# Sheet2.net
KiCad netlist of a schematic drawn in Altium Designer
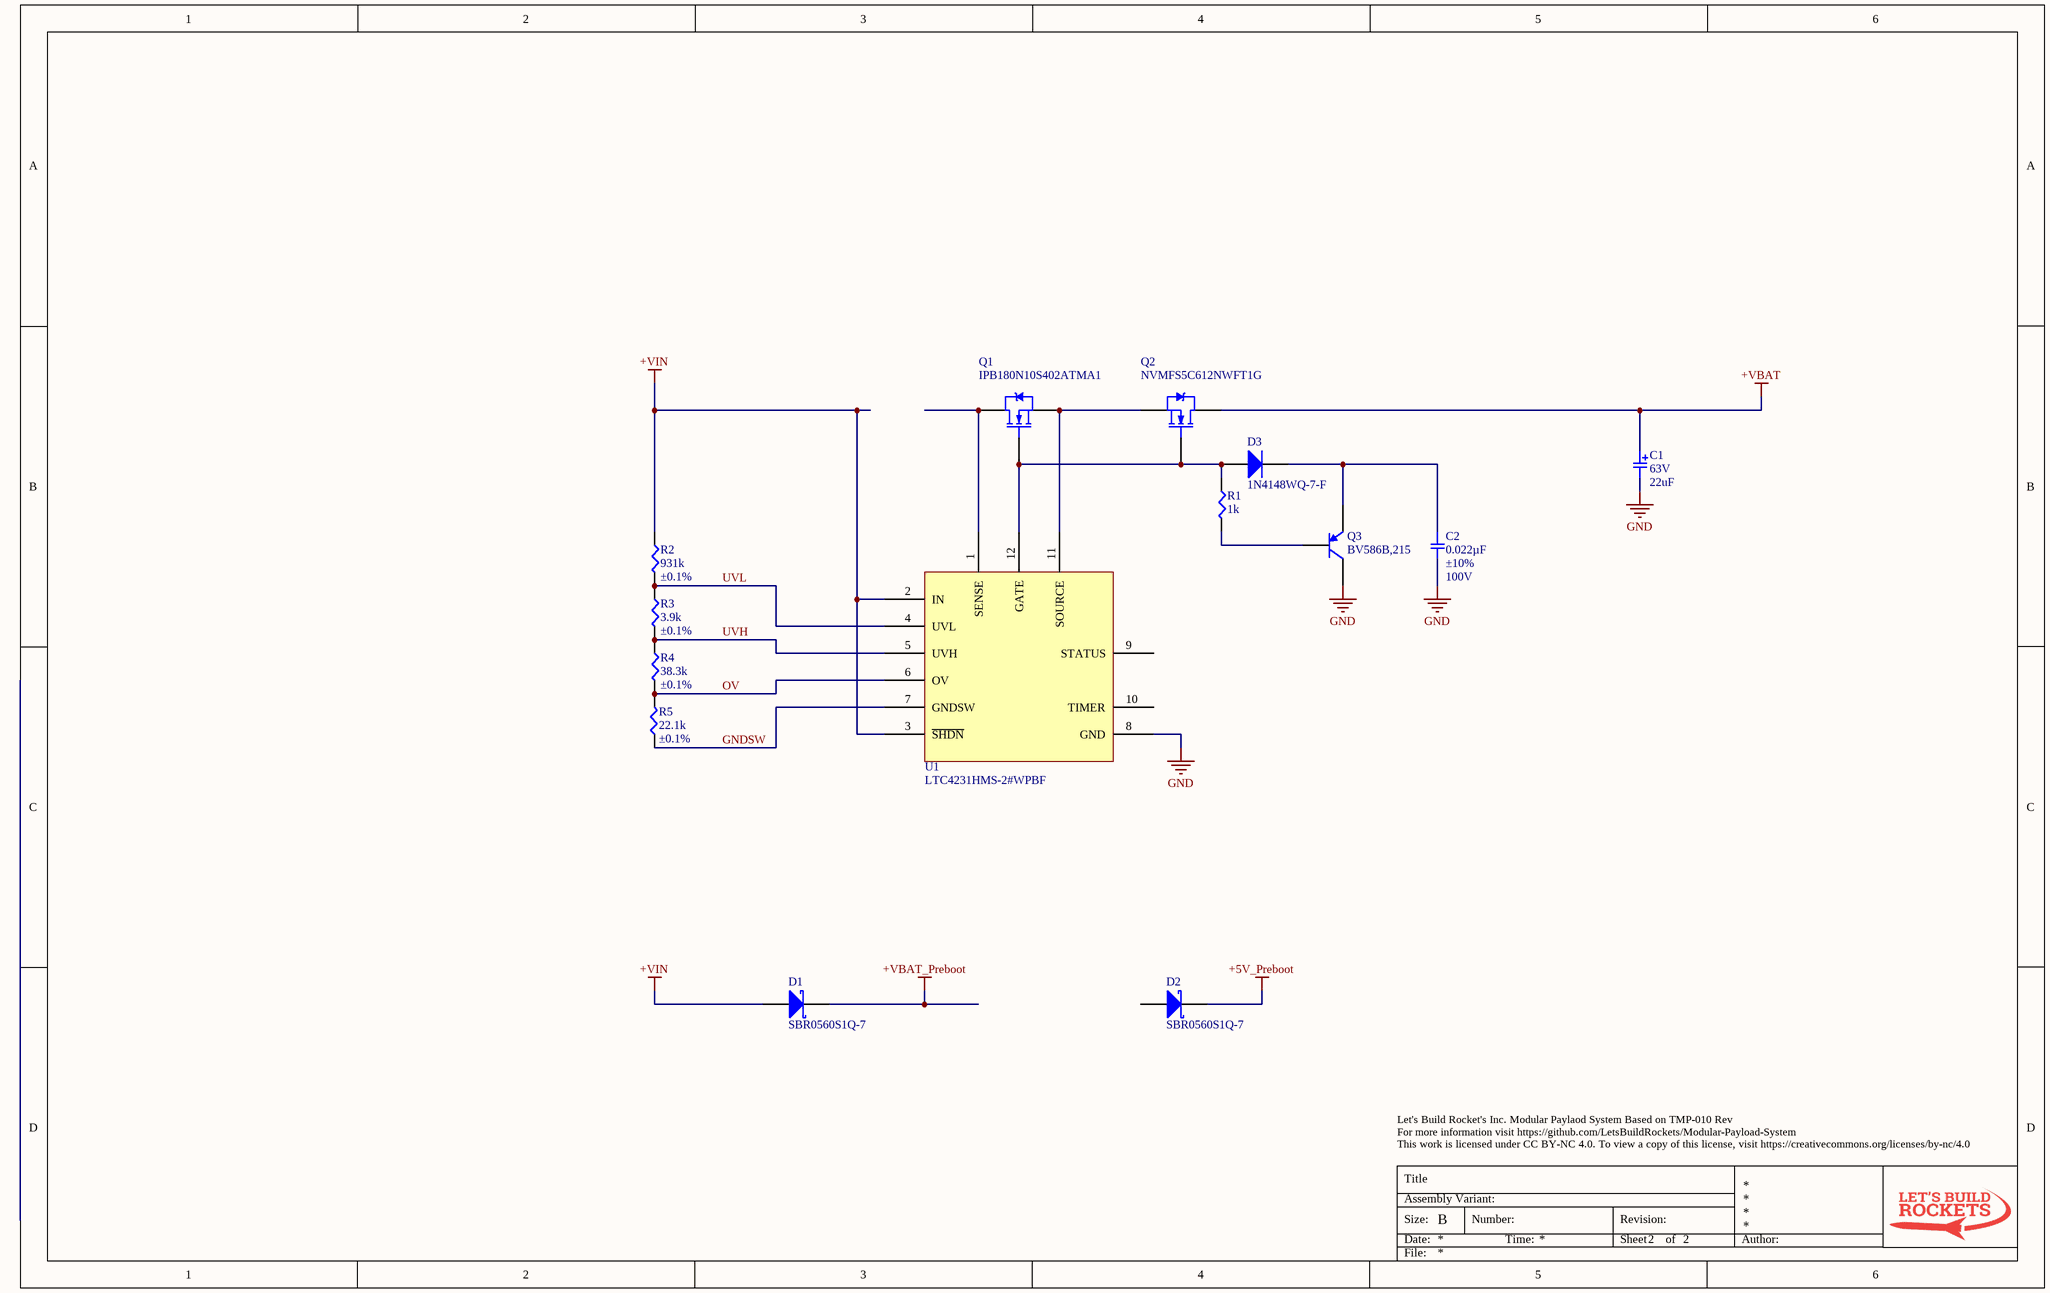
[diagram p0: Sheet2.SchDoc]

(export (version "E")
  (design (tool "Eeschema 10.0.6"))
  (components
    (comp (ref "C1")
      (value "22uF")
      (footprint "KEMET X - CAPMP7343X43N")
      (fields (field (name "VOLTAGE") "63V") (field (name "Comment") "T521X226M063ATE075"))
      (libsource (lib "KEMET") (part "T521X226M063ATE075"))
    )
    (comp (ref "C2")
      (value "0.022µF")
      (footprint "SMD-0603C")
      (description "CAP CER 0.022UF 100V X7R 0603")
      (fields
        (field (name "DIGI-KEY PART NUMBER") "490-5769-1-ND")
        (field (name "PART NUMBER") "GCJ188R72A223KA01D")
        (field (name "TOLERANCE") "±10%")
        (field (name "VOLTAGE") "100V")
      )
      (libsource (lib "capacitor_murata_0603") (part "GCJ188R72A223KA01D"))
    )
    (comp (ref "D1")
      (value "SBR0560S1Q-7")
      (footprint "SOD123")
      (libsource (lib "ModularPayload") (part "SBR0560S1Q-7"))
    )
    (comp (ref "D2")
      (value "SBR0560S1Q-7")
      (footprint "SOD123")
      (libsource (lib "ModularPayload") (part "SBR0560S1Q-7"))
    )
    (comp (ref "D3")
      (value "1N4148WQ-7-F")
      (footprint "SOD123")
      (libsource (lib "ModularPayload") (part "1N4148WQ-7-F"))
    )
    (comp (ref "Q1")
      (value "IPB180N10S402ATMA1")
      (footprint "DPAK127P1500X440-7N (PG-TO263-7-3)")
      (libsource (lib "ModularPayload") (part "IPB180N10S402ATMA1"))
    )
    (comp (ref "Q2") (value "NVMFS5C612NWFT1G") (libsource (lib "ModularPayload") (part "NVMFS5C612NWFT1G")))
    (comp (ref "Q3") (value "BV586B,215") (libsource (lib "ModularPayload") (part "BV586B,215")))
    (comp (ref "R1")
      (value "1k")
      (footprint "SMD-0402-RES")
      (description "RES SMD 1K OHM 5% 1/10W 0402")
      (fields (field (name "PART NUMBER") "ERJ-2GEJ102X") (field (name "DIGI-KEY PART NUMBER") "P1.0KJCT-ND"))
      (libsource (lib "Panasonic_ERJ_0402") (part "ERJ-2GEJ102X"))
    )
    (comp (ref "R2")
      (value "931k")
      (footprint "SMD-0805-RES")
      (description "RES SMD 931K OHM 0.1% 1/4W 0805")
      (fields
        (field (name "PART NUMBER") "ERJ-PB6B9313V")
        (field (name "DIGI-KEY PART NUMBER") "P20933CT-ND")
        (field (name "TOLERANCE") "±0.1%")
      )
      (libsource (lib "Panasonic_ERJ_0805") (part "ERJ-PB6B9313V"))
    )
    (comp (ref "R3")
      (value "3.9k")
      (footprint "SMD-0805-RES")
      (description "RES SMD 3.9K OHM 0.1% 1/4W 0805")
      (fields
        (field (name "PART NUMBER") "ERJ-PB6B3901V")
        (field (name "DIGI-KEY PART NUMBER") "P20660CT-ND")
        (field (name "TOLERANCE") "±0.1%")
      )
      (libsource (lib "Panasonic_ERJ_0805") (part "ERJ-PB6B3901V"))
    )
    (comp (ref "R4")
      (value "38.3k")
      (footprint "SMD-0805-RES")
      (description "RES SMD 38.3K OHM 0.1% 1/4W 0805")
      (fields
        (field (name "PART NUMBER") "ERJ-PB6B3832V")
        (field (name "DIGI-KEY PART NUMBER") "P20773CT-ND")
        (field (name "TOLERANCE") "±0.1%")
      )
      (libsource (lib "Panasonic_ERJ_0805") (part "ERJ-PB6B3832V"))
    )
    (comp (ref "R5")
      (value "22.1k")
      (footprint "SMD-0805-RES")
      (description "RES SMD 22.1K OHM 0.1% 1/4W 0805")
      (fields
        (field (name "PART NUMBER") "ERJ-PB6B2212V")
        (field (name "DIGI-KEY PART NUMBER") "P20745CT-ND")
        (field (name "TOLERANCE") "±0.1%")
      )
      (libsource (lib "Panasonic_ERJ_0805") (part "ERJ-PB6B2212V"))
    )
    (comp (ref "U1")
      (value "LTC4231HMS-2#WPBF")
      (footprint "TSOP65P490X109-12N")
      (libsource (lib "ModularPayload") (part "LTC4231HMS-2#WPBF"))
    )
  )
  (nets
    (net (code "1") (name "+5V_Preboot") (class "Default")
      (node (ref "D2") (pin "K") (pinfunction "K_K") (pintype "passive"))
    )
    (net (code "2") (name "+VBAT") (class "Default")
      (node (ref "C1") (pin "1") (pinfunction "1_1") (pintype "passive"))
      (node (ref "Q2") (pin "D") (pinfunction "D_D") (pintype "passive"))
    )
    (net (code "3") (name "+VBAT_Preboot") (class "Default")
      (node (ref "D1") (pin "K") (pinfunction "K_K") (pintype "passive"))
    )
    (net (code "4") (name "+VIN") (class "Default")
      (node (ref "D1") (pin "A") (pinfunction "A_A") (pintype "passive"))
      (node (ref "R2") (pin "1") (pinfunction "1_1") (pintype "passive"))
      (node (ref "U1") (pin "2") (pinfunction "IN_2") (pintype "passive"))
      (node (ref "U1") (pin "3") (pinfunction "~{SHDN}_3") (pintype "passive"))
    )
    (net (code "5") (name "/GNDSW") (class "Default")
      (node (ref "R5") (pin "1") (pinfunction "1_1") (pintype "passive"))
      (node (ref "U1") (pin "7") (pinfunction "GNDSW_7") (pintype "passive"))
    )
    (net (code "6") (name "/OV") (class "Default")
      (node (ref "R4") (pin "2") (pinfunction "2_2") (pintype "passive"))
      (node (ref "R5") (pin "2") (pinfunction "2_2") (pintype "passive"))
      (node (ref "U1") (pin "6") (pinfunction "OV_6") (pintype "passive"))
    )
    (net (code "7") (name "/UVH") (class "Default")
      (node (ref "R3") (pin "2") (pinfunction "2_2") (pintype "passive"))
      (node (ref "R4") (pin "1") (pinfunction "1_1") (pintype "passive"))
      (node (ref "U1") (pin "5") (pinfunction "UVH_5") (pintype "passive"))
    )
    (net (code "8") (name "/UVL") (class "Default")
      (node (ref "R2") (pin "2") (pinfunction "2_2") (pintype "passive"))
      (node (ref "R3") (pin "1") (pinfunction "1_1") (pintype "passive"))
      (node (ref "U1") (pin "4") (pinfunction "UVL_4") (pintype "passive"))
    )
    (net (code "9") (name "GND") (class "Default")
      (node (ref "C1") (pin "2") (pinfunction "2_2") (pintype "passive"))
      (node (ref "C2") (pin "2") (pinfunction "2_2") (pintype "passive"))
      (node (ref "Q3") (pin "C") (pinfunction "C_C") (pintype "passive"))
      (node (ref "U1") (pin "8") (pinfunction "GND_8") (pintype "passive"))
    )
    (net (code "10") (name "Net-(C2-Pad1)") (class "Default")
      (node (ref "C2") (pin "1") (pinfunction "1_1") (pintype "passive"))
      (node (ref "D3") (pin "K") (pinfunction "K_K") (pintype "passive"))
      (node (ref "Q3") (pin "E") (pinfunction "E_E") (pintype "passive"))
    )
    (net (code "11") (name "Net-(Q3-PadB)") (class "Default")
      (node (ref "Q3") (pin "B") (pinfunction "B_B") (pintype "passive"))
      (node (ref "R1") (pin "2") (pinfunction "2_2") (pintype "passive"))
    )
    (net (code "12") (name "Net-(U1-GATE)") (class "Default")
      (node (ref "D3") (pin "A") (pinfunction "A_A") (pintype "passive"))
      (node (ref "Q1") (pin "G") (pinfunction "G_G") (pintype "passive"))
      (node (ref "Q2") (pin "G") (pinfunction "G_G") (pintype "passive"))
      (node (ref "R1") (pin "1") (pinfunction "1_1") (pintype "passive"))
      (node (ref "U1") (pin "12") (pinfunction "GATE_12") (pintype "passive"))
    )
    (net (code "13") (name "Net-(U1-SENSE)") (class "Default")
      (node (ref "Q1") (pin "D") (pinfunction "D_D") (pintype "passive"))
      (node (ref "U1") (pin "1") (pinfunction "SENSE_1") (pintype "passive"))
    )
    (net (code "14") (name "Net-(U1-SOURCE)") (class "Default")
      (node (ref "Q1") (pin "S") (pinfunction "S_S") (pintype "passive"))
      (node (ref "Q2") (pin "S") (pinfunction "S_S") (pintype "passive"))
      (node (ref "U1") (pin "11") (pinfunction "SOURCE_11") (pintype "passive"))
    )
    (net (code "15") (name "unconnected-(D2-PadA)") (class "Default")
      (node (ref "D2") (pin "A") (pinfunction "A_A") (pintype "passive"))
    )
    (net (code "16") (name "unconnected-(U1-STATUS-Pad9)") (class "Default")
      (node (ref "U1") (pin "9") (pinfunction "STATUS_9") (pintype "passive"))
    )
    (net (code "17") (name "unconnected-(U1-TIMER-Pad10)") (class "Default")
      (node (ref "U1") (pin "10") (pinfunction "TIMER_10") (pintype "passive"))
    )
  )
)
